# PCBv2_5a.net
KiCad netlist of a schematic drawn in EasyEDA
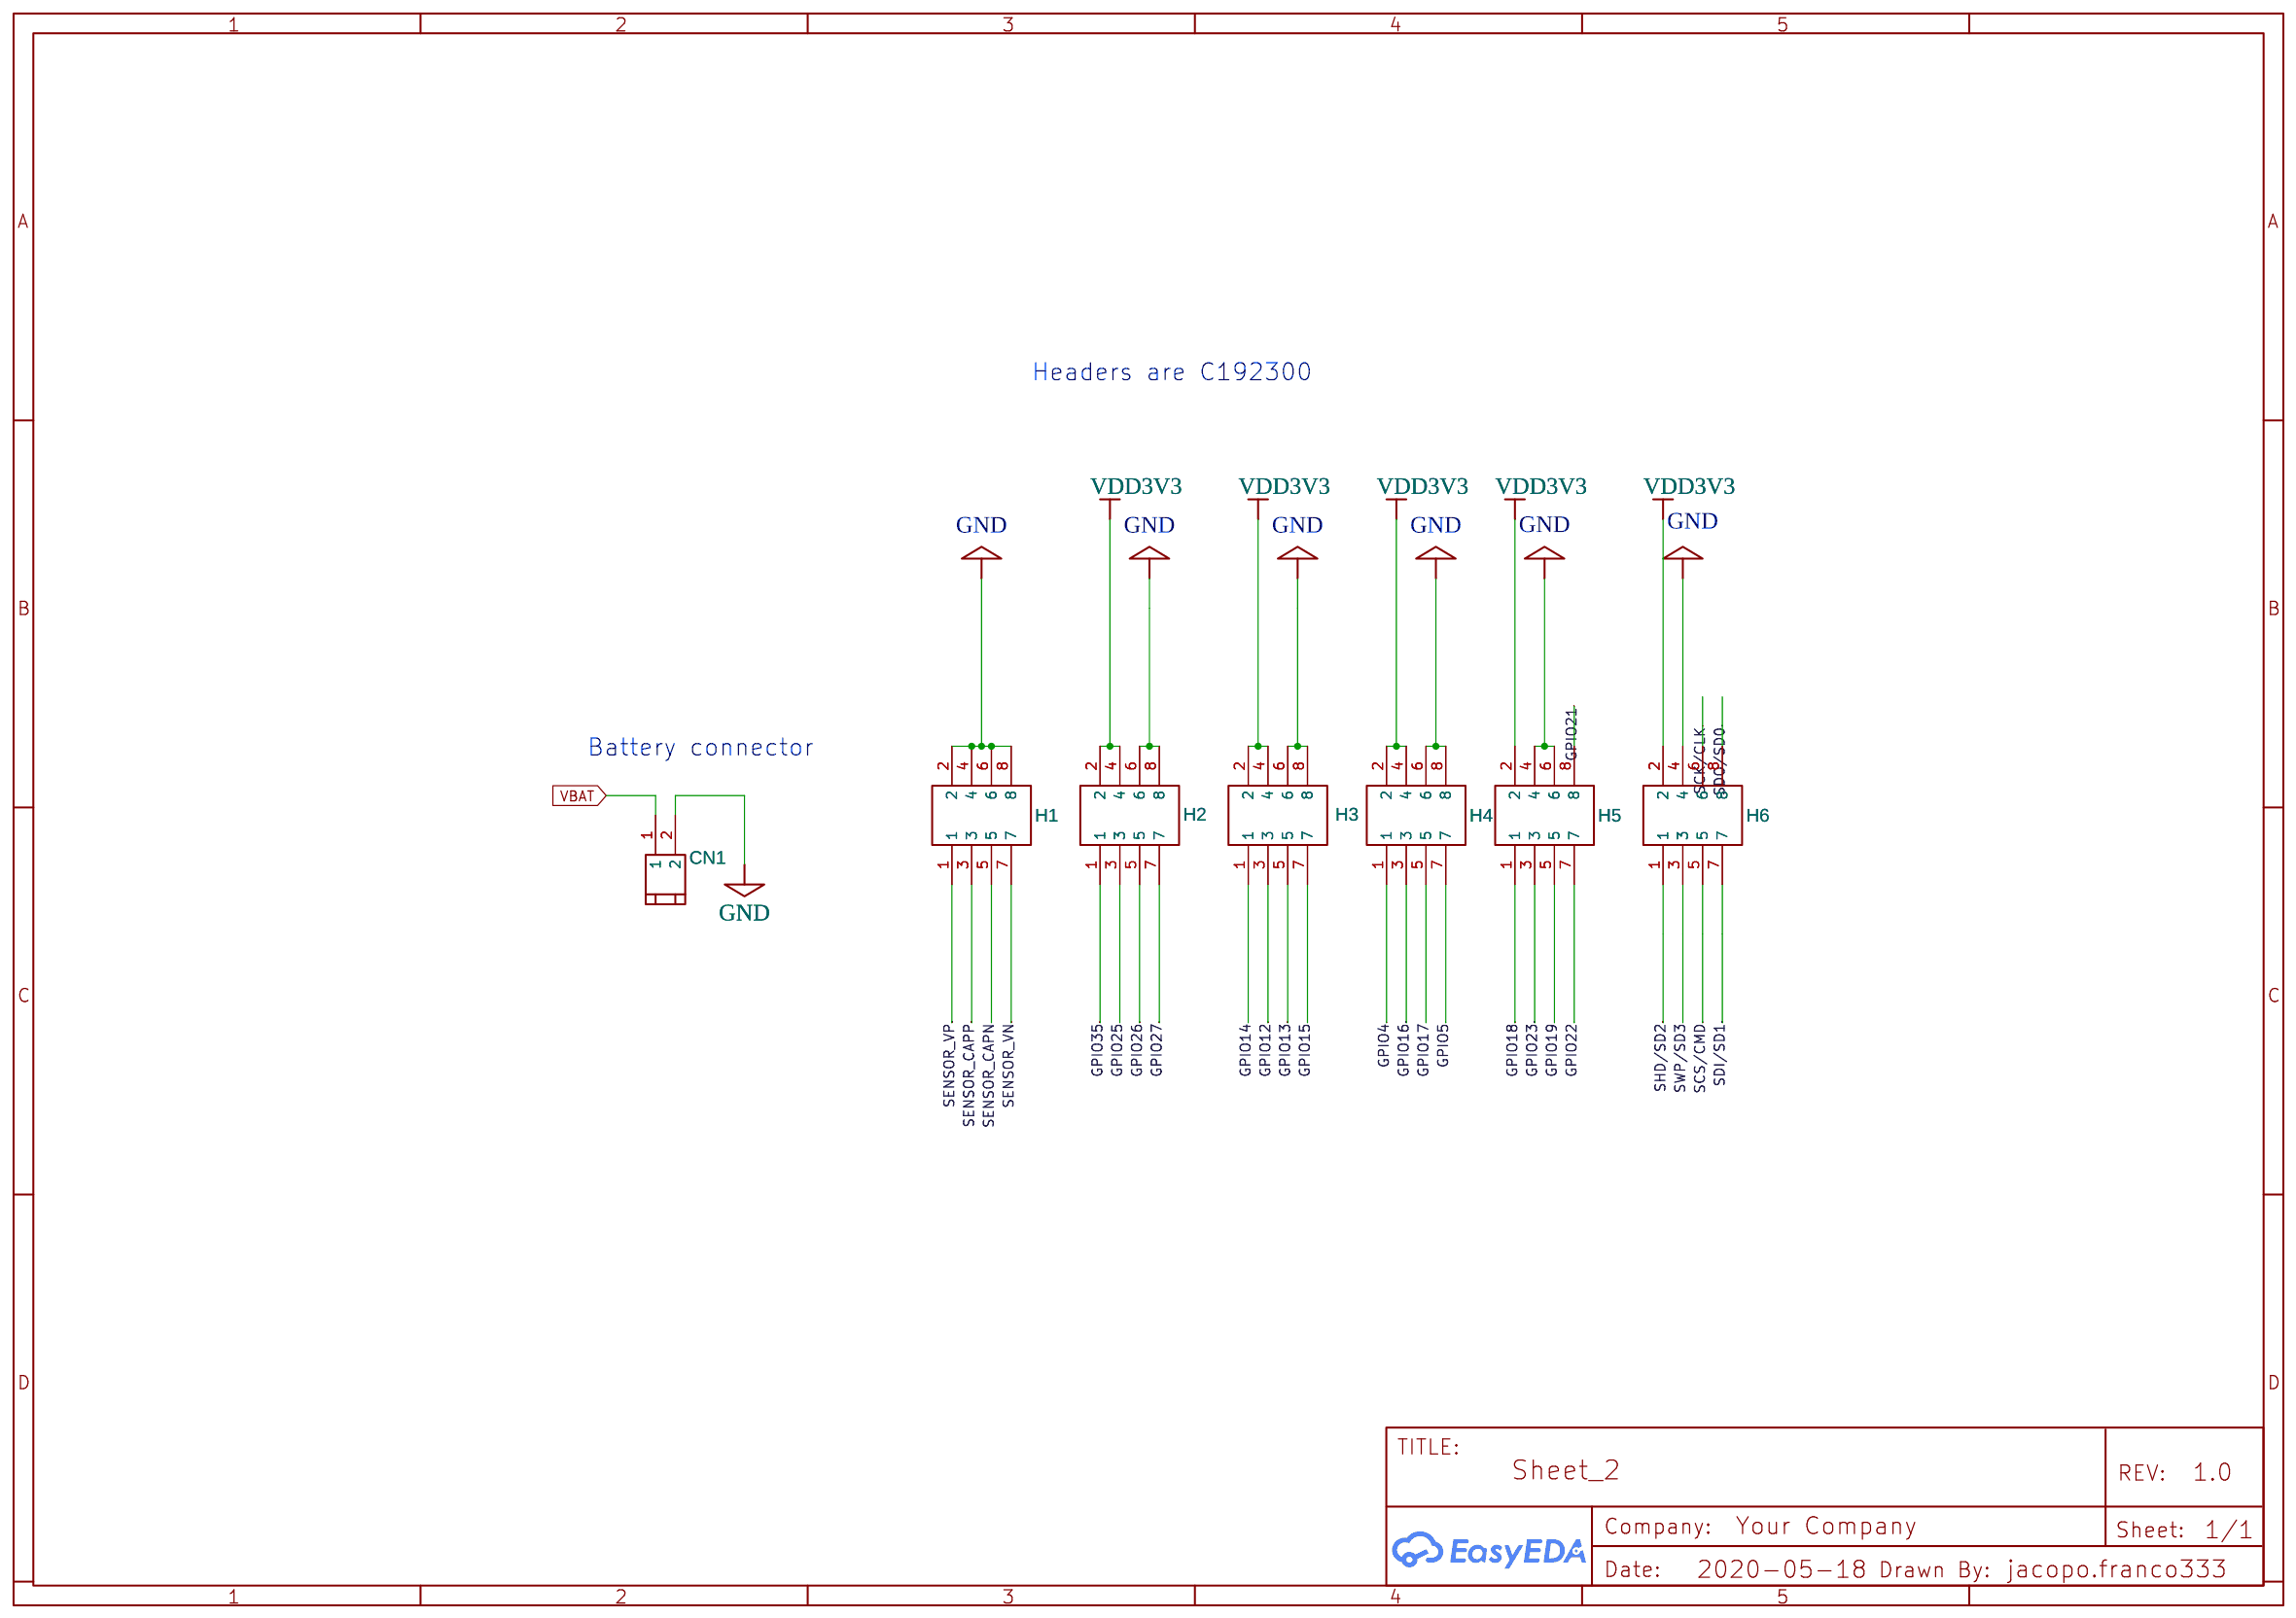
[diagram p0: Headers]
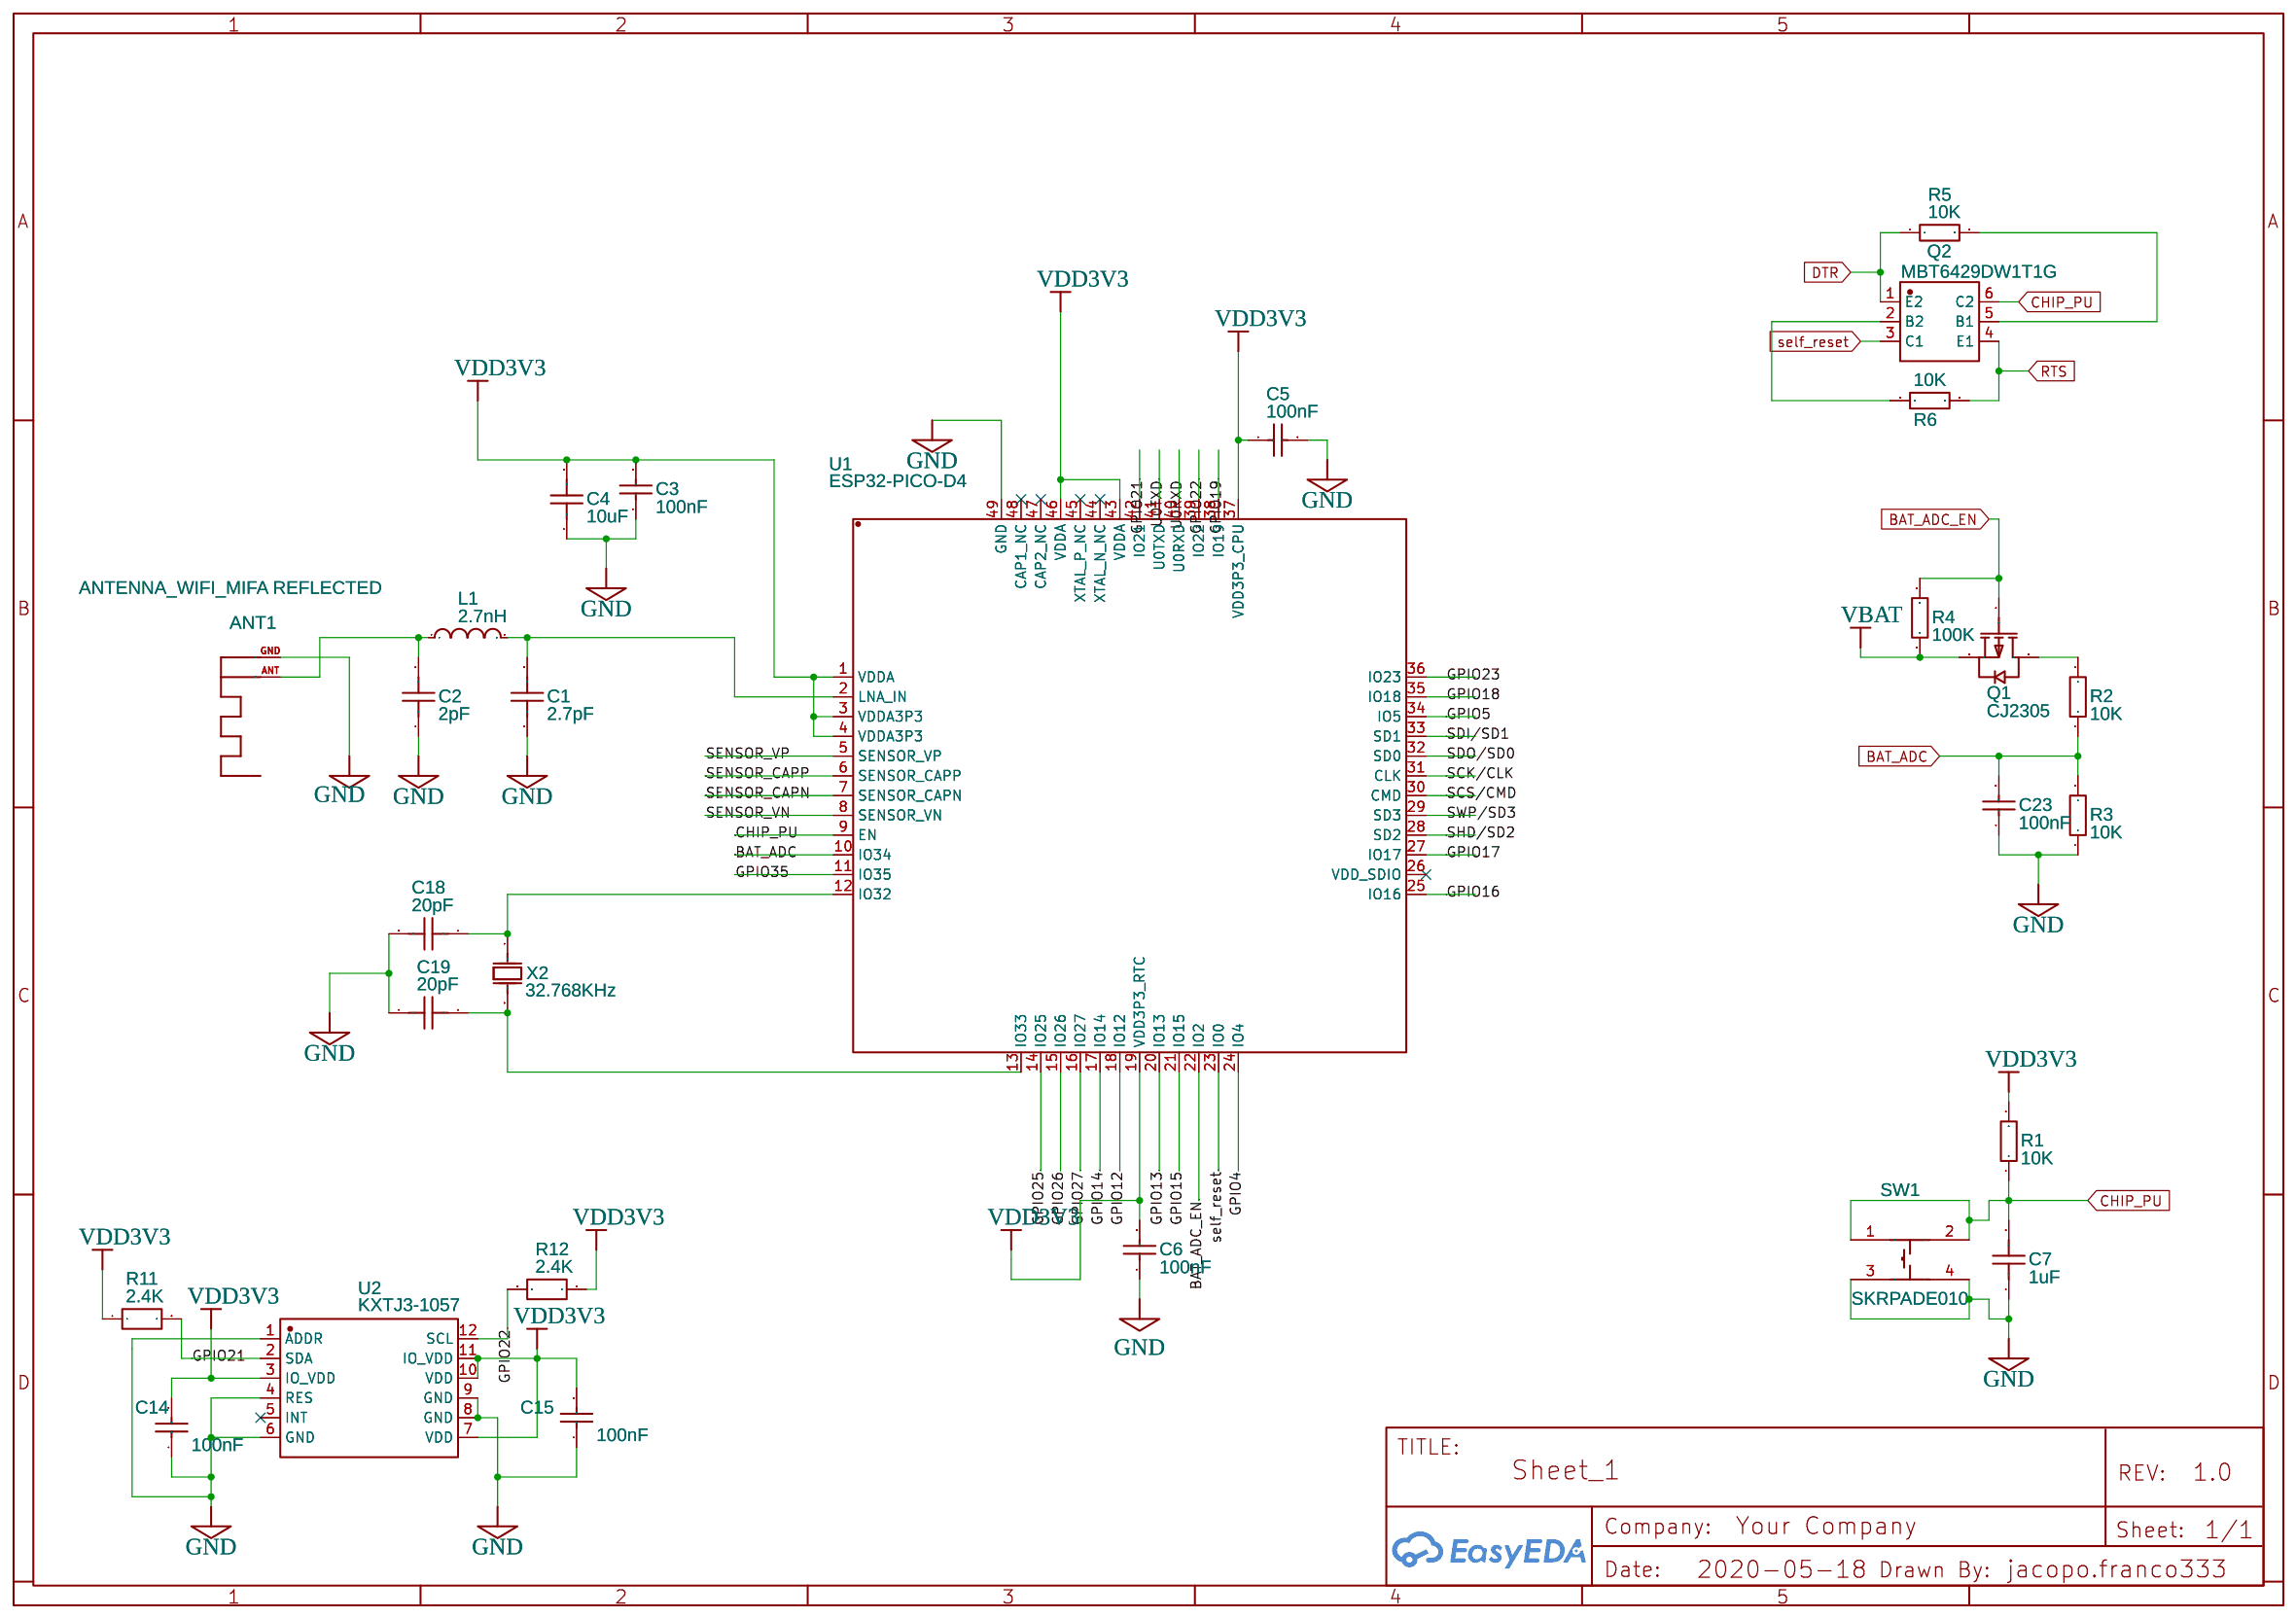
[diagram p1: ESP32]
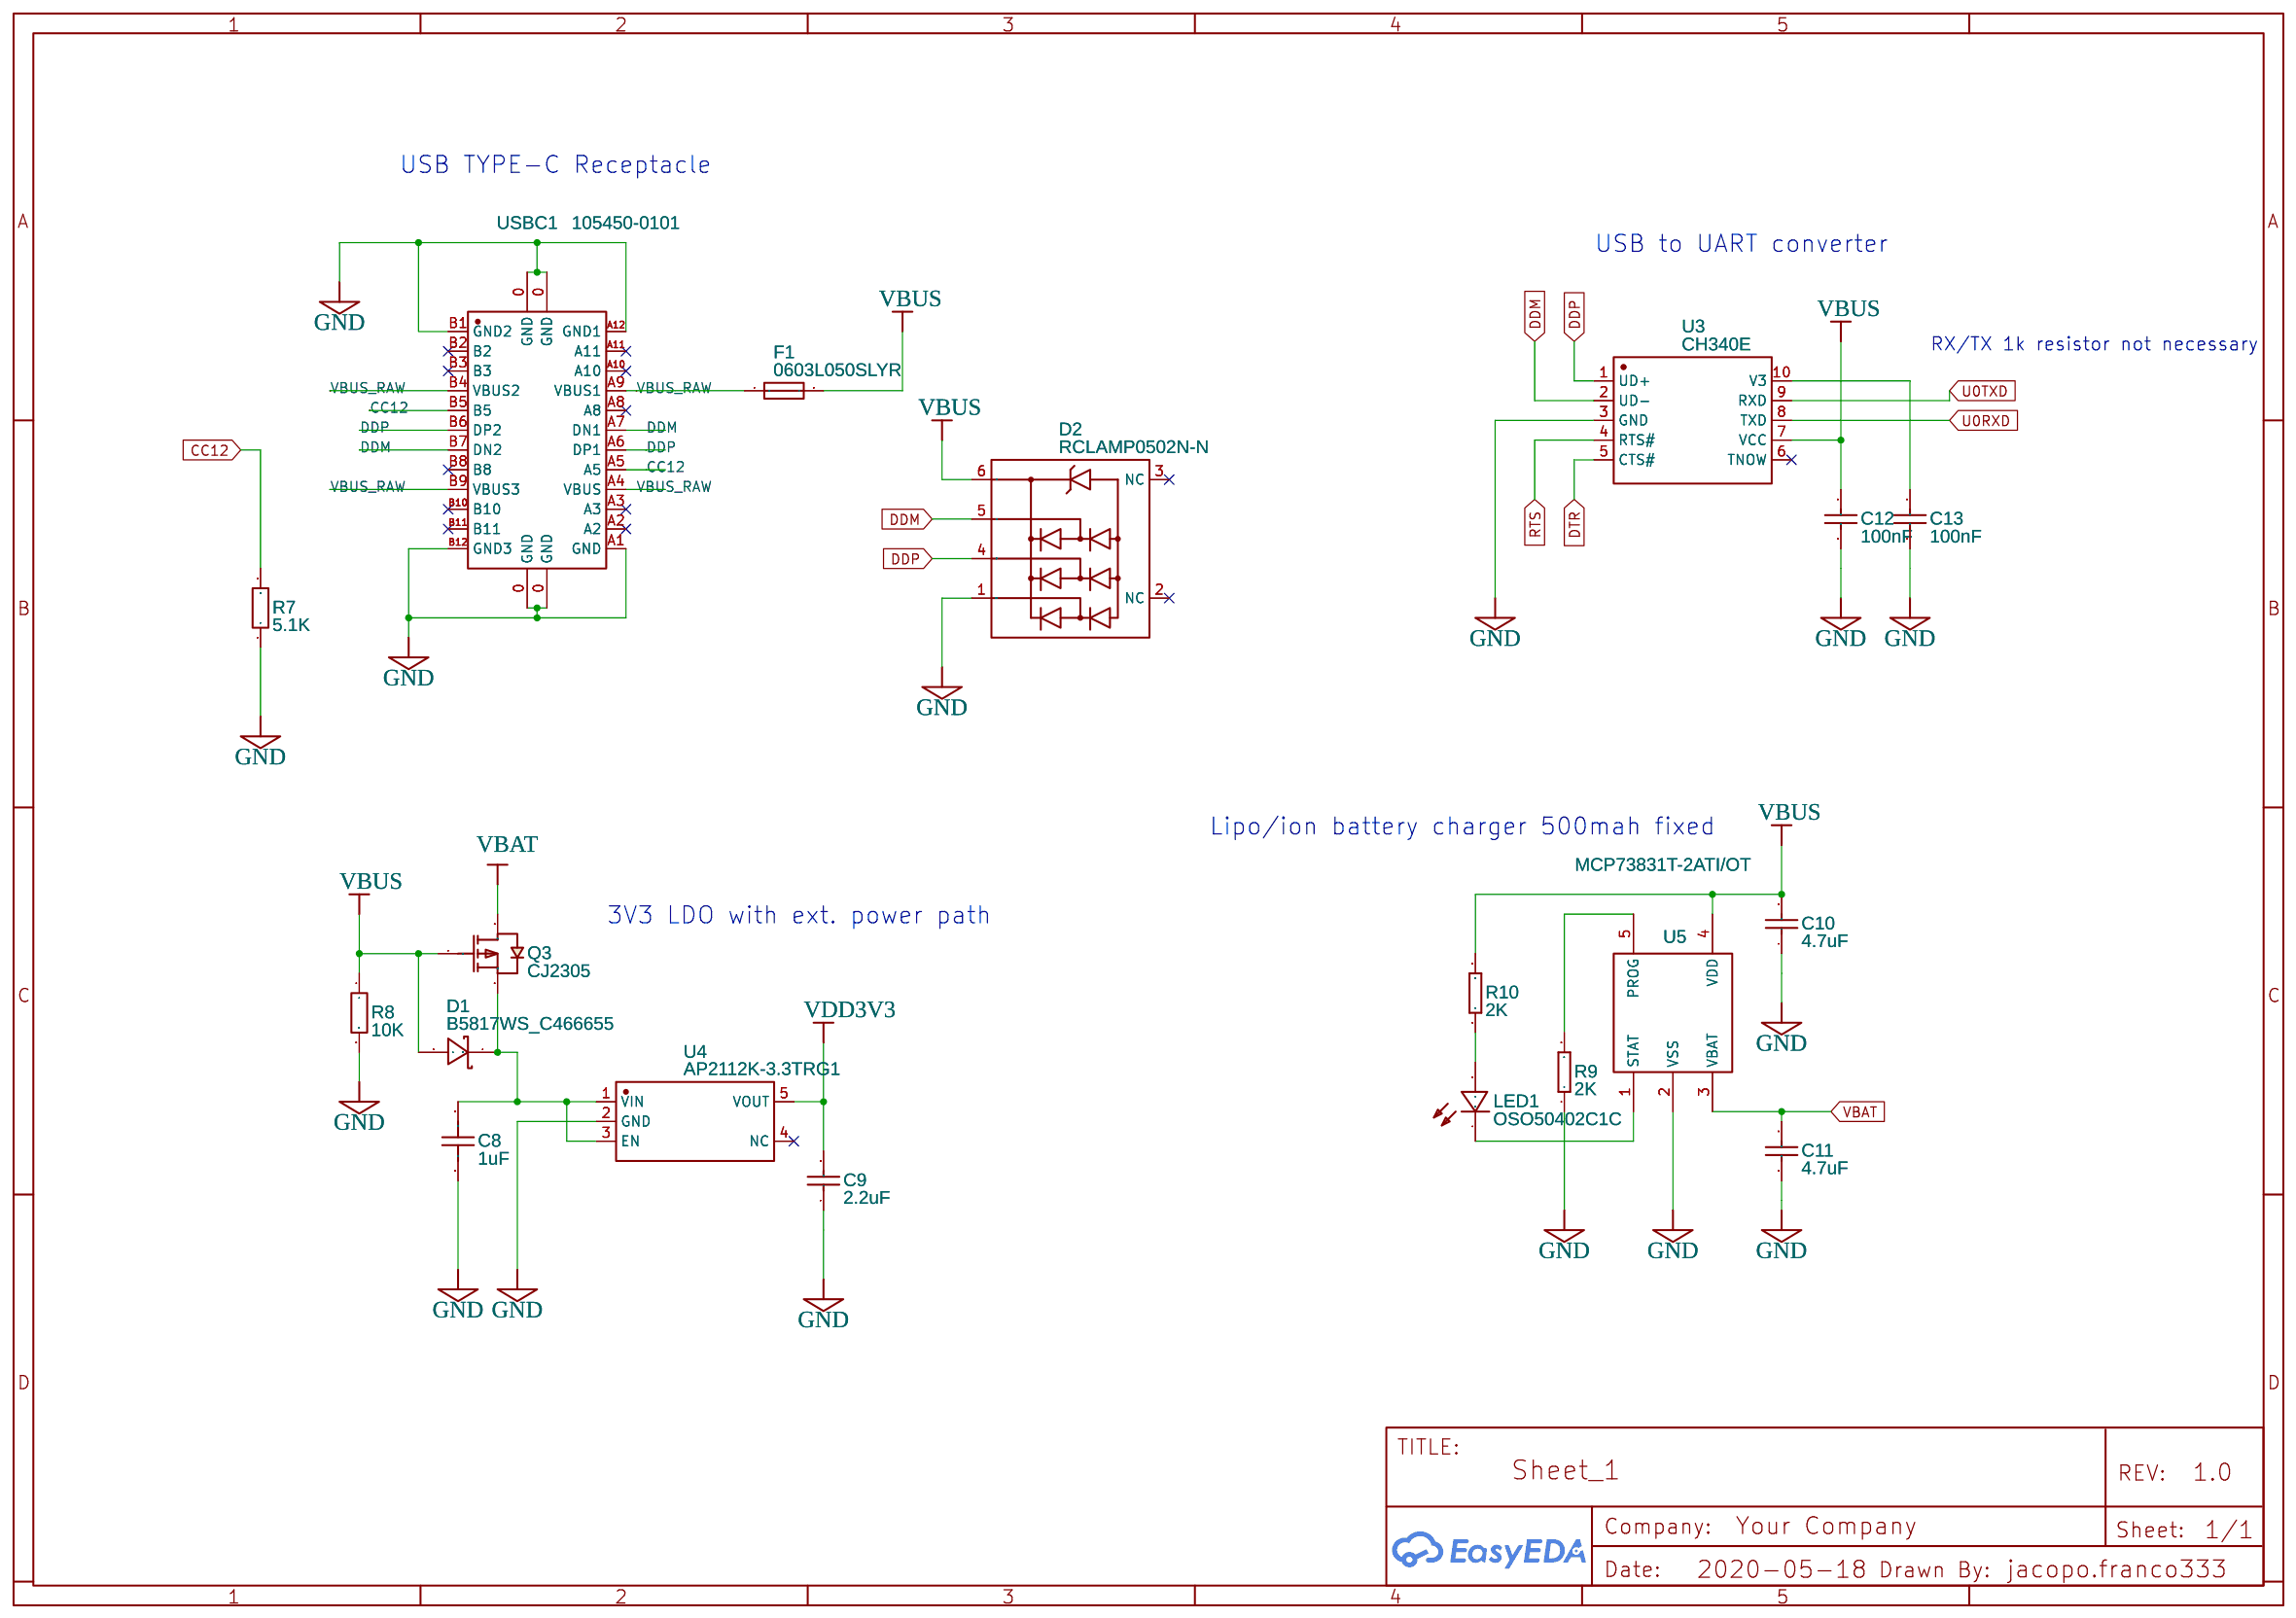
[diagram p2: Power, USB]

(export (version "E")
  (design (tool "Eeschema 10.0.6"))
  (components
    (comp (ref "CN1")
      (value "XH-2PWB")
      (fields (field (name "BOM_Supplier Part") "C64520"))
      (libsource (lib "") (part "XH-2PWB"))
    )
    (comp (ref "H1")
      (value "95278-801A08LF")
      (fields (field (name "BOM_Supplier Part") "C192300"))
      (libsource (lib "") (part "95278-801A08LF"))
    )
    (comp (ref "H2")
      (value "95278-801A08LF")
      (fields (field (name "BOM_Supplier Part") "C192300"))
      (libsource (lib "") (part "95278-801A08LF"))
    )
    (comp (ref "H3")
      (value "95278-801A08LF")
      (fields (field (name "BOM_Supplier Part") "C192300"))
      (libsource (lib "") (part "95278-801A08LF"))
    )
    (comp (ref "H4")
      (value "95278-801A08LF")
      (fields (field (name "BOM_Supplier Part") "C192300"))
      (libsource (lib "") (part "95278-801A08LF"))
    )
    (comp (ref "H5")
      (value "95278-801A08LF")
      (fields (field (name "BOM_Supplier Part") "C192300"))
      (libsource (lib "") (part "95278-801A08LF"))
    )
    (comp (ref "H6")
      (value "95278-801A08LF")
      (fields (field (name "BOM_Supplier Part") "C192300"))
      (libsource (lib "") (part "95278-801A08LF"))
    )
    (comp (ref "ANT1")
      (value "ANTENNA_WIFI_MIFA REFLECTED")
      (libsource (lib "") (part "ANTENNA_WIFI_MIFA REFLECTED"))
    )
    (comp (ref "C1")
      (value "2.7pF")
      (fields
        (field (name "BOM_Manufacturer Part") "CC0402CRNPO9BN2R7")
        (field (name "BOM_Supplier Part") "C277484")
      )
      (libsource (lib "") (part "CC0402CRNPO9BN2R7"))
    )
    (comp (ref "C2")
      (value "2pF")
      (fields
        (field (name "BOM_Manufacturer Part") "GJM1555C1H2R0WB01D")
        (field (name "BOM_Supplier Part") "C88885")
      )
      (libsource (lib "") (part "GJM1555C1H2R0WB01D"))
    )
    (comp (ref "C3")
      (value "100nF")
      (fields
        (field (name "BOM_Manufacturer Part") "GCM155R71E104KE02D")
        (field (name "BOM_Supplier Part") "C126527")
      )
      (libsource (lib "") (part "GCM155R71E104KE02D"))
    )
    (comp (ref "C4")
      (value "10uF")
      (fields
        (field (name "BOM_Manufacturer Part") "GRM155R61A106ME21D")
        (field (name "BOM_Supplier Part") "C324476")
      )
      (libsource (lib "") (part "GRM155R61A106ME21D"))
    )
    (comp (ref "C5")
      (value "100nF")
      (fields
        (field (name "BOM_Manufacturer Part") "GCM155R71E104KE02D")
        (field (name "BOM_Supplier Part") "C126527")
      )
      (libsource (lib "") (part "GCM155R71E104KE02D_1"))
    )
    (comp (ref "C6")
      (value "100nF")
      (fields
        (field (name "BOM_Manufacturer Part") "GCM155R71E104KE02D")
        (field (name "BOM_Supplier Part") "C126527")
      )
      (libsource (lib "") (part "GCM155R71E104KE02D"))
    )
    (comp (ref "C7")
      (value "1uF")
      (fields
        (field (name "BOM_Manufacturer Part") "CL05A105KA5NQNC")
        (field (name "BOM_Supplier Part") "C52923")
      )
      (libsource (lib "") (part "CL05A105KA5NQNC"))
    )
    (comp (ref "C14")
      (value "100nF")
      (fields
        (field (name "BOM_Manufacturer Part") "GCM155R71E104KE02D")
        (field (name "BOM_Supplier Part") "C126527")
      )
      (libsource (lib "") (part "GCM155R71E104KE02D"))
    )
    (comp (ref "C15")
      (value "100nF")
      (fields
        (field (name "BOM_Manufacturer Part") "GCM155R71E104KE02D")
        (field (name "BOM_Supplier Part") "C126527")
      )
      (libsource (lib "") (part "GCM155R71E104KE02D"))
    )
    (comp (ref "C18")
      (value "20pF")
      (fields
        (field (name "BOM_Manufacturer Part") "GCM1555C1H200FA16D")
        (field (name "BOM_Supplier Part") "C437436")
      )
      (libsource (lib "") (part "GCM1555C1H200FA16D_1"))
    )
    (comp (ref "C19")
      (value "20pF")
      (fields
        (field (name "BOM_Manufacturer Part") "GCM1555C1H200FA16D")
        (field (name "BOM_Supplier Part") "C437436")
      )
      (libsource (lib "") (part "GCM1555C1H200FA16D"))
    )
    (comp (ref "C23")
      (value "100nF")
      (fields
        (field (name "BOM_Manufacturer Part") "GCM155R71E104KE02D")
        (field (name "BOM_Supplier Part") "C126527")
      )
      (libsource (lib "") (part "GCM155R71E104KE02D"))
    )
    (comp (ref "L1")
      (value "2.7nH")
      (fields
        (field (name "BOM_Manufacturer Part") "MLG1005S2N7BT000")
        (field (name "BOM_Supplier Part") "C275282")
      )
      (libsource (lib "") (part "MLG1005S2N7BT000"))
    )
    (comp (ref "Q1")
      (value "CJ2305")
      (fields (field (name "BOM_Supplier Part") "C8549"))
      (libsource (lib "") (part "CJ2305"))
    )
    (comp (ref "Q2")
      (value "MBT6429DW1T1G")
      (fields (field (name "BOM_Supplier Part") "C463297"))
      (libsource (lib "") (part "MBT6429DW1T1G"))
    )
    (comp (ref "R1")
      (value "10K")
      (fields
        (field (name "BOM_Manufacturer Part") "RC0402FR-0710KL")
        (field (name "BOM_Supplier Part") "C60490")
      )
      (libsource (lib "") (part "RC0402FR-0710KL"))
    )
    (comp (ref "R2")
      (value "10K")
      (fields
        (field (name "BOM_Manufacturer Part") "RC0402FR-0710KL")
        (field (name "BOM_Supplier Part") "C60490")
      )
      (libsource (lib "") (part "RC0402FR-0710KL"))
    )
    (comp (ref "R3")
      (value "10K")
      (fields
        (field (name "BOM_Manufacturer Part") "RC0402FR-0710KL")
        (field (name "BOM_Supplier Part") "C60490")
      )
      (libsource (lib "") (part "RC0402FR-0710KL"))
    )
    (comp (ref "R4")
      (value "100K")
      (fields
        (field (name "BOM_Manufacturer Part") "0402WGJ0104TCE")
        (field (name "BOM_Supplier Part") "C25530")
      )
      (libsource (lib "") (part "0402WGJ0104TCE"))
    )
    (comp (ref "R5")
      (value "10K")
      (fields
        (field (name "BOM_Manufacturer Part") "RC0402FR-0710KL")
        (field (name "BOM_Supplier Part") "C60490")
      )
      (libsource (lib "") (part "RC0402FR-0710KL_1"))
    )
    (comp (ref "R6")
      (value "10K")
      (fields
        (field (name "BOM_Manufacturer Part") "RC0402FR-0710KL")
        (field (name "BOM_Supplier Part") "C60490")
      )
      (libsource (lib "") (part "RC0402FR-0710KL_1"))
    )
    (comp (ref "R11")
      (value "2.4K")
      (fields
        (field (name "BOM_Manufacturer Part") "0402WGD2401TCE")
        (field (name "BOM_Supplier Part") "C407742")
      )
      (libsource (lib "") (part "0402WGD2401TCE_1"))
    )
    (comp (ref "R12")
      (value "2.4K")
      (fields
        (field (name "BOM_Manufacturer Part") "0402WGD2401TCE")
        (field (name "BOM_Supplier Part") "C407742")
      )
      (libsource (lib "") (part "0402WGD2401TCE"))
    )
    (comp (ref "SW1")
      (value "SKRPADE010")
      (fields (field (name "BOM_Supplier Part") "C127488"))
      (libsource (lib "") (part "SKRPADE010"))
    )
    (comp (ref "U1")
      (value "ESP32-PICO-D4")
      (fields (field (name "BOM_Supplier Part") "C193707"))
      (libsource (lib "") (part "ESP32-PICO-D4"))
    )
    (comp (ref "U2")
      (value "KXTJ3-1057")
      (fields (field (name "BOM_Supplier Part") "C442603"))
      (libsource (lib "") (part "KXTJ3-1057"))
    )
    (comp (ref "X2")
      (value "32.768KHz")
      (fields
        (field (name "BOM_Manufacturer Part") "AH03270014")
        (field (name "BOM_Supplier Part") "C409356")
      )
      (libsource (lib "") (part "AH03270014"))
    )
    (comp (ref "C8")
      (value "1uF")
      (fields
        (field (name "BOM_Manufacturer Part") "CL05A105KA5NQNC")
        (field (name "BOM_Supplier Part") "C52923")
      )
      (libsource (lib "") (part "CL05A105KA5NQNC"))
    )
    (comp (ref "C9")
      (value "2.2uF")
      (fields
        (field (name "BOM_Manufacturer Part") "GRM155R61A225KE95D")
        (field (name "BOM_Supplier Part") "C77002")
      )
      (libsource (lib "") (part "GRM155R61A225KE95D"))
    )
    (comp (ref "C10")
      (value "4.7uF")
      (fields
        (field (name "BOM_Manufacturer Part") "GRM155R61A475KEAAD")
        (field (name "BOM_Supplier Part") "C77004")
      )
      (libsource (lib "") (part "GRM155R61A475KEAAD"))
    )
    (comp (ref "C11")
      (value "4.7uF")
      (fields
        (field (name "BOM_Manufacturer Part") "GRM155R61A475KEAAD")
        (field (name "BOM_Supplier Part") "C77004")
      )
      (libsource (lib "") (part "GRM155R61A475KEAAD"))
    )
    (comp (ref "C12")
      (value "100nF")
      (fields
        (field (name "BOM_Manufacturer Part") "GCM155R71E104KE02D")
        (field (name "BOM_Supplier Part") "C126527")
      )
      (libsource (lib "") (part "GCM155R71E104KE02D"))
    )
    (comp (ref "C13")
      (value "100nF")
      (fields
        (field (name "BOM_Manufacturer Part") "GCM155R71E104KE02D")
        (field (name "BOM_Supplier Part") "C126527")
      )
      (libsource (lib "") (part "GCM155R71E104KE02D"))
    )
    (comp (ref "D1")
      (value "B5817WS_C466655")
      (fields (field (name "BOM_Manufacturer Part") "B5817WS") (field (name "BOM_Supplier Part") "C466655"))
      (libsource (lib "") (part "B5817WS_C466655"))
    )
    (comp (ref "D2")
      (value "RCLAMP0502N-N")
      (fields
        (field (name "BOM_Manufacturer Part") "Rclamp0502N-N")
        (field (name "BOM_Supplier Part") "C344005")
      )
      (libsource (lib "") (part "RCLAMP0502N-N"))
    )
    (comp (ref "F1")
      (value "0603L050SLYR")
      (fields (field (name "BOM_Supplier Part") "C207014"))
      (libsource (lib "") (part "0603L050SLYR"))
    )
    (comp (ref "LED1")
      (value "OSO50402C1C")
      (fields (field (name "BOM_Supplier Part") "C268301"))
      (libsource (lib "") (part "OSO50402C1C"))
    )
    (comp (ref "Q3")
      (value "CJ2305")
      (fields (field (name "BOM_Supplier Part") "C8549"))
      (libsource (lib "") (part "CJ2305"))
    )
    (comp (ref "R7")
      (value "5.1K")
      (fields
        (field (name "BOM_Manufacturer Part") "AR02DTD5101")
        (field (name "BOM_Supplier Part") "C319557")
      )
      (libsource (lib "") (part "AR02DTD5101"))
    )
    (comp (ref "R8")
      (value "10K")
      (fields
        (field (name "BOM_Manufacturer Part") "RC0402FR-0710KL")
        (field (name "BOM_Supplier Part") "C60490")
      )
      (libsource (lib "") (part "RC0402FR-0710KL"))
    )
    (comp (ref "R9")
      (value "2K")
      (fields (field (name "BOM_Supplier Part") "C478870"))
      (libsource (lib "") (part "RESISTOR-0402"))
    )
    (comp (ref "R10")
      (value "2K")
      (fields (field (name "BOM_Supplier Part") "C478870"))
      (libsource (lib "") (part "RESISTOR-0402"))
    )
    (comp (ref "U3")
      (value "CH340E")
      (fields (field (name "BOM_Supplier Part") "C99652"))
      (libsource (lib "") (part "CH340E"))
    )
    (comp (ref "U4")
      (value "AP2112K-3.3TRG1")
      (fields (field (name "BOM_Supplier Part") "C51118"))
      (libsource (lib "") (part "AP2112K-3.3TRG1"))
    )
    (comp (ref "U5")
      (value "MCP73831T-2ATI/OT")
      (fields (field (name "BOM_Supplier Part") "C14879"))
      (libsource (lib "") (part "MCP73831T-2ATI/OT"))
    )
    (comp (ref "USBC1")
      (value "105450-0101")
      (fields (field (name "BOM_Supplier Part") "C134092"))
      (libsource (lib "") (part "105450-0101"))
    )
  )
  (nets
    (net (code "1") (name "BAT_ADC") (class "Default")
      (node (ref "C23") (pin "2") (pinfunction "2_2") (pintype "input"))
      (node (ref "R2") (pin "1") (pinfunction "1_1") (pintype "input"))
      (node (ref "R3") (pin "2") (pinfunction "2_2") (pintype "input"))
      (node (ref "U1") (pin "10") (pinfunction "IO34_10") (pintype "unspecified"))
    )
    (net (code "2") (name "BAT_ADC_EN") (class "Default")
      (node (ref "Q1") (pin "1") (pinfunction "G_1") (pintype "unspecified"))
      (node (ref "R4") (pin "2") (pinfunction "2_2") (pintype "input"))
      (node (ref "U1") (pin "22") (pinfunction "IO2_22") (pintype "unspecified"))
    )
    (net (code "3") (name "CC12") (class "Default")
      (node (ref "R7") (pin "2") (pinfunction "2_2") (pintype "unspecified"))
      (node (ref "USBC1") (pin "A5") (pinfunction "A5_A5") (pintype "unspecified"))
      (node (ref "USBC1") (pin "B5") (pinfunction "B5_B5") (pintype "unspecified"))
    )
    (net (code "4") (name "CHIP_PU") (class "Default")
      (node (ref "C7") (pin "2") (pinfunction "2_2") (pintype "unspecified"))
      (node (ref "Q2") (pin "6") (pinfunction "C2_6") (pintype "unspecified"))
      (node (ref "R1") (pin "1") (pinfunction "1_1") (pintype "input"))
      (node (ref "SW1") (pin "1") (pinfunction "1_1") (pintype "unspecified"))
      (node (ref "SW1") (pin "2") (pinfunction "2_2") (pintype "unspecified"))
      (node (ref "U1") (pin "9") (pinfunction "EN_9") (pintype "unspecified"))
    )
    (net (code "5") (name "DDM") (class "Default")
      (node (ref "D2") (pin "5") (pinfunction "I/O_5") (pintype "unspecified"))
      (node (ref "U3") (pin "2") (pinfunction "UD-_2") (pintype "unspecified"))
      (node (ref "USBC1") (pin "A7") (pinfunction "DN1_A7") (pintype "unspecified"))
      (node (ref "USBC1") (pin "B7") (pinfunction "DN2_B7") (pintype "unspecified"))
    )
    (net (code "6") (name "DDP") (class "Default")
      (node (ref "D2") (pin "4") (pinfunction "I/O_4") (pintype "unspecified"))
      (node (ref "U3") (pin "1") (pinfunction "UD+_1") (pintype "unspecified"))
      (node (ref "USBC1") (pin "A6") (pinfunction "DP1_A6") (pintype "unspecified"))
      (node (ref "USBC1") (pin "B6") (pinfunction "DP2_B6") (pintype "unspecified"))
    )
    (net (code "7") (name "DTR") (class "Default")
      (node (ref "Q2") (pin "1") (pinfunction "E2_1") (pintype "unspecified"))
      (node (ref "R5") (pin "1") (pinfunction "1_1") (pintype "input"))
      (node (ref "U3") (pin "5") (pinfunction "CTS#_5") (pintype "unspecified"))
    )
    (net (code "8") (name "GND") (class "Default")
      (node (ref "ANT1") (pin "GND") (pinfunction "GND_GND") (pintype "unspecified"))
      (node (ref "C1") (pin "1") (pinfunction "1_1") (pintype "unspecified"))
      (node (ref "C10") (pin "1") (pinfunction "1_1") (pintype "input"))
      (node (ref "C11") (pin "1") (pinfunction "1_1") (pintype "input"))
      (node (ref "C12") (pin "1") (pinfunction "1_1") (pintype "input"))
      (node (ref "C13") (pin "1") (pinfunction "1_1") (pintype "input"))
      (node (ref "C14") (pin "1") (pinfunction "1_1") (pintype "input"))
      (node (ref "C15") (pin "1") (pinfunction "1_1") (pintype "input"))
      (node (ref "C18") (pin "2") (pinfunction "2_2") (pintype "unspecified"))
      (node (ref "C19") (pin "1") (pinfunction "1_1") (pintype "unspecified"))
      (node (ref "C2") (pin "1") (pinfunction "1_1") (pintype "unspecified"))
      (node (ref "C23") (pin "1") (pinfunction "1_1") (pintype "input"))
      (node (ref "C3") (pin "1") (pinfunction "1_1") (pintype "input"))
      (node (ref "C4") (pin "1") (pinfunction "1_1") (pintype "unspecified"))
      (node (ref "C5") (pin "2") (pinfunction "2_2") (pintype "input"))
      (node (ref "C6") (pin "1") (pinfunction "1_1") (pintype "input"))
      (node (ref "C7") (pin "1") (pinfunction "1_1") (pintype "unspecified"))
      (node (ref "C8") (pin "1") (pinfunction "1_1") (pintype "unspecified"))
      (node (ref "C9") (pin "1") (pinfunction "1_1") (pintype "input"))
      (node (ref "CN1") (pin "2") (pinfunction "2_2") (pintype "unspecified"))
      (node (ref "D2") (pin "1") (pinfunction "GND_1") (pintype "unspecified"))
      (node (ref "H1") (pin "2") (pinfunction "2_2") (pintype "unspecified"))
      (node (ref "H1") (pin "4") (pinfunction "4_4") (pintype "unspecified"))
      (node (ref "H1") (pin "6") (pinfunction "6_6") (pintype "unspecified"))
      (node (ref "H1") (pin "8") (pinfunction "8_8") (pintype "unspecified"))
      (node (ref "H2") (pin "6") (pinfunction "6_6") (pintype "unspecified"))
      (node (ref "H2") (pin "8") (pinfunction "8_8") (pintype "unspecified"))
      (node (ref "H3") (pin "6") (pinfunction "6_6") (pintype "unspecified"))
      (node (ref "H3") (pin "8") (pinfunction "8_8") (pintype "unspecified"))
      (node (ref "H4") (pin "6") (pinfunction "6_6") (pintype "unspecified"))
      (node (ref "H4") (pin "8") (pinfunction "8_8") (pintype "unspecified"))
      (node (ref "H5") (pin "4") (pinfunction "4_4") (pintype "unspecified"))
      (node (ref "H5") (pin "6") (pinfunction "6_6") (pintype "unspecified"))
      (node (ref "H6") (pin "4") (pinfunction "4_4") (pintype "unspecified"))
      (node (ref "R3") (pin "1") (pinfunction "1_1") (pintype "input"))
      (node (ref "R7") (pin "1") (pinfunction "1_1") (pintype "unspecified"))
      (node (ref "R8") (pin "2") (pinfunction "2_2") (pintype "input"))
      (node (ref "R9") (pin "1") (pinfunction "1_1") (pintype "unspecified"))
      (node (ref "SW1") (pin "3") (pinfunction "3_3") (pintype "unspecified"))
      (node (ref "SW1") (pin "4") (pinfunction "4_4") (pintype "unspecified"))
      (node (ref "U1") (pin "49") (pinfunction "GND_49") (pintype "unspecified"))
      (node (ref "U2") (pin "1") (pinfunction "ADDR_1") (pintype "unspecified"))
      (node (ref "U2") (pin "4") (pinfunction "RES_4") (pintype "unspecified"))
      (node (ref "U2") (pin "6") (pinfunction "GND_6") (pintype "unspecified"))
      (node (ref "U2") (pin "8") (pinfunction "GND_8") (pintype "unspecified"))
      (node (ref "U2") (pin "9") (pinfunction "GND_9") (pintype "unspecified"))
      (node (ref "U3") (pin "3") (pinfunction "GND_3") (pintype "unspecified"))
      (node (ref "U4") (pin "2") (pinfunction "GND_2") (pintype "unspecified"))
      (node (ref "U5") (pin "2") (pinfunction "VSS_2") (pintype "unspecified"))
      (node (ref "USBC1") (pin "0") (pinfunction "GND_0") (pintype "unspecified"))
      (node (ref "USBC1") (pin "A1") (pinfunction "GND_A1") (pintype "unspecified"))
      (node (ref "USBC1") (pin "A12") (pinfunction "GND1_A12") (pintype "unspecified"))
      (node (ref "USBC1") (pin "B1") (pinfunction "GND2_B1") (pintype "unspecified"))
      (node (ref "USBC1") (pin "B12") (pinfunction "GND3_B12") (pintype "unspecified"))
    )
    (net (code "9") (name "GPIO4") (class "Default")
      (node (ref "H4") (pin "1") (pinfunction "1_1") (pintype "unspecified"))
      (node (ref "U1") (pin "24") (pinfunction "IO4_24") (pintype "unspecified"))
    )
    (net (code "10") (name "GPIO5") (class "Default")
      (node (ref "H4") (pin "7") (pinfunction "7_7") (pintype "unspecified"))
      (node (ref "U1") (pin "34") (pinfunction "IO5_34") (pintype "unspecified"))
    )
    (net (code "11") (name "GPIO12") (class "Default")
      (node (ref "H3") (pin "3") (pinfunction "3_3") (pintype "unspecified"))
      (node (ref "U1") (pin "18") (pinfunction "IO12_18") (pintype "unspecified"))
    )
    (net (code "12") (name "GPIO13") (class "Default")
      (node (ref "H3") (pin "5") (pinfunction "5_5") (pintype "unspecified"))
      (node (ref "U1") (pin "20") (pinfunction "IO13_20") (pintype "unspecified"))
    )
    (net (code "13") (name "GPIO14") (class "Default")
      (node (ref "H3") (pin "1") (pinfunction "1_1") (pintype "unspecified"))
      (node (ref "U1") (pin "17") (pinfunction "IO14_17") (pintype "unspecified"))
    )
    (net (code "14") (name "GPIO15") (class "Default")
      (node (ref "H3") (pin "7") (pinfunction "7_7") (pintype "unspecified"))
      (node (ref "U1") (pin "21") (pinfunction "IO15_21") (pintype "unspecified"))
    )
    (net (code "15") (name "GPIO16") (class "Default")
      (node (ref "H4") (pin "3") (pinfunction "3_3") (pintype "unspecified"))
      (node (ref "U1") (pin "25") (pinfunction "IO16_25") (pintype "unspecified"))
    )
    (net (code "16") (name "GPIO17") (class "Default")
      (node (ref "H4") (pin "5") (pinfunction "5_5") (pintype "unspecified"))
      (node (ref "U1") (pin "27") (pinfunction "IO17_27") (pintype "unspecified"))
    )
    (net (code "17") (name "GPIO18") (class "Default")
      (node (ref "H5") (pin "1") (pinfunction "1_1") (pintype "unspecified"))
      (node (ref "U1") (pin "35") (pinfunction "IO18_35") (pintype "unspecified"))
    )
    (net (code "18") (name "GPIO19") (class "Default")
      (node (ref "H5") (pin "5") (pinfunction "5_5") (pintype "unspecified"))
      (node (ref "U1") (pin "38") (pinfunction "IO19_38") (pintype "unspecified"))
    )
    (net (code "19") (name "GPIO21") (class "Default")
      (node (ref "H5") (pin "8") (pinfunction "8_8") (pintype "unspecified"))
      (node (ref "R11") (pin "2") (pinfunction "2_2") (pintype "unspecified"))
      (node (ref "U1") (pin "42") (pinfunction "IO21_42") (pintype "unspecified"))
      (node (ref "U2") (pin "2") (pinfunction "SDA_2") (pintype "unspecified"))
    )
    (net (code "20") (name "GPIO22") (class "Default")
      (node (ref "H5") (pin "7") (pinfunction "7_7") (pintype "unspecified"))
      (node (ref "R12") (pin "2") (pinfunction "2_2") (pintype "unspecified"))
      (node (ref "U1") (pin "39") (pinfunction "IO22_39") (pintype "unspecified"))
      (node (ref "U2") (pin "12") (pinfunction "SCL_12") (pintype "unspecified"))
    )
    (net (code "21") (name "GPIO23") (class "Default")
      (node (ref "H5") (pin "3") (pinfunction "3_3") (pintype "unspecified"))
      (node (ref "U1") (pin "36") (pinfunction "IO23_36") (pintype "unspecified"))
    )
    (net (code "22") (name "GPIO25") (class "Default")
      (node (ref "H2") (pin "3") (pinfunction "3_3") (pintype "unspecified"))
      (node (ref "U1") (pin "14") (pinfunction "IO25_14") (pintype "unspecified"))
    )
    (net (code "23") (name "GPIO26") (class "Default")
      (node (ref "H2") (pin "5") (pinfunction "5_5") (pintype "unspecified"))
      (node (ref "U1") (pin "15") (pinfunction "IO26_15") (pintype "unspecified"))
    )
    (net (code "24") (name "GPIO27") (class "Default")
      (node (ref "H2") (pin "7") (pinfunction "7_7") (pintype "unspecified"))
      (node (ref "U1") (pin "16") (pinfunction "IO27_16") (pintype "unspecified"))
    )
    (net (code "25") (name "GPIO35") (class "Default")
      (node (ref "H2") (pin "1") (pinfunction "1_1") (pintype "unspecified"))
      (node (ref "U1") (pin "11") (pinfunction "IO35_11") (pintype "unspecified"))
    )
    (net (code "26") (name "Net-(ANT1-PadANT)") (class "Default")
      (node (ref "ANT1") (pin "ANT") (pinfunction "ANT_ANT") (pintype "unspecified"))
      (node (ref "C2") (pin "2") (pinfunction "2_2") (pintype "unspecified"))
      (node (ref "L1") (pin "1") (pinfunction "1_1") (pintype "unspecified"))
    )
    (net (code "27") (name "Net-(D1-C)") (class "Default")
      (node (ref "C8") (pin "2") (pinfunction "2_2") (pintype "unspecified"))
      (node (ref "D1") (pin "1") (pinfunction "C_1") (pintype "unspecified"))
      (node (ref "Q3") (pin "2") (pinfunction "S_2") (pintype "unspecified"))
      (node (ref "U4") (pin "1") (pinfunction "VIN_1") (pintype "unspecified"))
      (node (ref "U4") (pin "3") (pinfunction "EN_3") (pintype "unspecified"))
    )
    (net (code "28") (name "Net-(LED1-A)") (class "Default")
      (node (ref "LED1") (pin "2") (pinfunction "A_2") (pintype "unspecified"))
      (node (ref "R10") (pin "1") (pinfunction "1_1") (pintype "unspecified"))
    )
    (net (code "29") (name "Net-(LED1-C)") (class "Default")
      (node (ref "LED1") (pin "1") (pinfunction "C_1") (pintype "unspecified"))
      (node (ref "U5") (pin "1") (pinfunction "STAT_1") (pintype "unspecified"))
    )
    (net (code "30") (name "Net-(Q1-D)") (class "Default")
      (node (ref "Q1") (pin "3") (pinfunction "D_3") (pintype "unspecified"))
      (node (ref "R2") (pin "2") (pinfunction "2_2") (pintype "input"))
    )
    (net (code "31") (name "Net-(Q2-B1)") (class "Default")
      (node (ref "Q2") (pin "5") (pinfunction "B1_5") (pintype "unspecified"))
      (node (ref "R5") (pin "2") (pinfunction "2_2") (pintype "input"))
    )
    (net (code "32") (name "Net-(Q2-B2)") (class "Default")
      (node (ref "Q2") (pin "2") (pinfunction "B2_2") (pintype "unspecified"))
      (node (ref "R6") (pin "1") (pinfunction "1_1") (pintype "input"))
    )
    (net (code "33") (name "Net-(U1-IO32)") (class "Default")
      (node (ref "C18") (pin "1") (pinfunction "1_1") (pintype "unspecified"))
      (node (ref "U1") (pin "12") (pinfunction "IO32_12") (pintype "unspecified"))
      (node (ref "X2") (pin "1") (pinfunction "OSC1_1") (pintype "input"))
    )
    (net (code "34") (name "Net-(U1-IO33)") (class "Default")
      (node (ref "C19") (pin "2") (pinfunction "2_2") (pintype "unspecified"))
      (node (ref "U1") (pin "13") (pinfunction "IO33_13") (pintype "unspecified"))
      (node (ref "X2") (pin "2") (pinfunction "OSC2_2") (pintype "input"))
    )
    (net (code "35") (name "Net-(U1-LNA_IN)") (class "Default")
      (node (ref "C1") (pin "2") (pinfunction "2_2") (pintype "unspecified"))
      (node (ref "L1") (pin "2") (pinfunction "2_2") (pintype "unspecified"))
      (node (ref "U1") (pin "2") (pinfunction "LNA_IN_2") (pintype "unspecified"))
    )
    (net (code "36") (name "Net-(U3-V3)") (class "Default")
      (node (ref "C13") (pin "2") (pinfunction "2_2") (pintype "input"))
      (node (ref "U3") (pin "10") (pinfunction "V3_10") (pintype "unspecified"))
    )
    (net (code "37") (name "Net-(U5-PROG)") (class "Default")
      (node (ref "R9") (pin "2") (pinfunction "2_2") (pintype "unspecified"))
      (node (ref "U5") (pin "5") (pinfunction "PROG_5") (pintype "unspecified"))
    )
    (net (code "38") (name "RTS") (class "Default")
      (node (ref "Q2") (pin "4") (pinfunction "E1_4") (pintype "unspecified"))
      (node (ref "R6") (pin "2") (pinfunction "2_2") (pintype "input"))
      (node (ref "U3") (pin "4") (pinfunction "RTS#_4") (pintype "unspecified"))
    )
    (net (code "39") (name "SCK{slash}CLK") (class "Default")
      (node (ref "H6") (pin "6") (pinfunction "6_6") (pintype "unspecified"))
      (node (ref "U1") (pin "31") (pinfunction "CLK_31") (pintype "unspecified"))
    )
    (net (code "40") (name "SCS{slash}CMD") (class "Default")
      (node (ref "H6") (pin "5") (pinfunction "5_5") (pintype "unspecified"))
      (node (ref "U1") (pin "30") (pinfunction "CMD_30") (pintype "unspecified"))
    )
    (net (code "41") (name "SDI{slash}SD1") (class "Default")
      (node (ref "H6") (pin "7") (pinfunction "7_7") (pintype "unspecified"))
      (node (ref "U1") (pin "33") (pinfunction "SD1_33") (pintype "unspecified"))
    )
    (net (code "42") (name "SDO{slash}SD0") (class "Default")
      (node (ref "H6") (pin "8") (pinfunction "8_8") (pintype "unspecified"))
      (node (ref "U1") (pin "32") (pinfunction "SD0_32") (pintype "unspecified"))
    )
    (net (code "43") (name "SENSOR_CAPN") (class "Default")
      (node (ref "H1") (pin "5") (pinfunction "5_5") (pintype "unspecified"))
      (node (ref "U1") (pin "7") (pinfunction "SENSOR_CAPN_7") (pintype "unspecified"))
    )
    (net (code "44") (name "SENSOR_CAPP") (class "Default")
      (node (ref "H1") (pin "3") (pinfunction "3_3") (pintype "unspecified"))
      (node (ref "U1") (pin "6") (pinfunction "SENSOR_CAPP_6") (pintype "unspecified"))
    )
    (net (code "45") (name "SENSOR_VN") (class "Default")
      (node (ref "H1") (pin "7") (pinfunction "7_7") (pintype "unspecified"))
      (node (ref "U1") (pin "8") (pinfunction "SENSOR_VN_8") (pintype "unspecified"))
    )
    (net (code "46") (name "SENSOR_VP") (class "Default")
      (node (ref "H1") (pin "1") (pinfunction "1_1") (pintype "unspecified"))
      (node (ref "U1") (pin "5") (pinfunction "SENSOR_VP_5") (pintype "unspecified"))
    )
    (net (code "47") (name "SHD{slash}SD2") (class "Default")
      (node (ref "H6") (pin "1") (pinfunction "1_1") (pintype "unspecified"))
      (node (ref "U1") (pin "28") (pinfunction "SD2_28") (pintype "unspecified"))
    )
    (net (code "48") (name "SWP{slash}SD3") (class "Default")
      (node (ref "H6") (pin "3") (pinfunction "3_3") (pintype "unspecified"))
      (node (ref "U1") (pin "29") (pinfunction "SD3_29") (pintype "unspecified"))
    )
    (net (code "49") (name "U0RXD") (class "Default")
      (node (ref "U1") (pin "40") (pinfunction "U0RXD_40") (pintype "unspecified"))
      (node (ref "U3") (pin "8") (pinfunction "TXD_8") (pintype "unspecified"))
    )
    (net (code "50") (name "U0TXD") (class "Default")
      (node (ref "U1") (pin "41") (pinfunction "U0TXD_41") (pintype "unspecified"))
      (node (ref "U3") (pin "9") (pinfunction "RXD_9") (pintype "unspecified"))
    )
    (net (code "51") (name "VBAT") (class "Default")
      (node (ref "C11") (pin "2") (pinfunction "2_2") (pintype "input"))
      (node (ref "CN1") (pin "1") (pinfunction "1_1") (pintype "unspecified"))
      (node (ref "Q1") (pin "2") (pinfunction "S_2") (pintype "unspecified"))
      (node (ref "Q3") (pin "3") (pinfunction "D_3") (pintype "unspecified"))
      (node (ref "R4") (pin "1") (pinfunction "1_1") (pintype "input"))
      (node (ref "U5") (pin "3") (pinfunction "VBAT_3") (pintype "unspecified"))
    )
    (net (code "52") (name "VBUS") (class "Default")
      (node (ref "C10") (pin "2") (pinfunction "2_2") (pintype "input"))
      (node (ref "C12") (pin "2") (pinfunction "2_2") (pintype "input"))
      (node (ref "D1") (pin "2") (pinfunction "A_2") (pintype "unspecified"))
      (node (ref "D2") (pin "6") (pinfunction "VBUS_6") (pintype "unspecified"))
      (node (ref "F1") (pin "2") (pinfunction "2_2") (pintype "unspecified"))
      (node (ref "Q3") (pin "1") (pinfunction "G_1") (pintype "unspecified"))
      (node (ref "R10") (pin "2") (pinfunction "2_2") (pintype "unspecified"))
      (node (ref "R8") (pin "1") (pinfunction "1_1") (pintype "input"))
      (node (ref "U3") (pin "7") (pinfunction "VCC_7") (pintype "unspecified"))
      (node (ref "U5") (pin "4") (pinfunction "VDD_4") (pintype "unspecified"))
    )
    (net (code "53") (name "VBUS_RAW") (class "Default")
      (node (ref "F1") (pin "1") (pinfunction "1_1") (pintype "unspecified"))
      (node (ref "USBC1") (pin "A4") (pinfunction "VBUS_A4") (pintype "unspecified"))
      (node (ref "USBC1") (pin "A9") (pinfunction "VBUS1_A9") (pintype "unspecified"))
      (node (ref "USBC1") (pin "B4") (pinfunction "VBUS2_B4") (pintype "unspecified"))
      (node (ref "USBC1") (pin "B9") (pinfunction "VBUS3_B9") (pintype "unspecified"))
    )
    (net (code "54") (name "VDD3V3") (class "Default")
      (node (ref "C14") (pin "2") (pinfunction "2_2") (pintype "input"))
      (node (ref "C15") (pin "2") (pinfunction "2_2") (pintype "input"))
      (node (ref "C3") (pin "2") (pinfunction "2_2") (pintype "input"))
      (node (ref "C4") (pin "2") (pinfunction "2_2") (pintype "unspecified"))
      (node (ref "C5") (pin "1") (pinfunction "1_1") (pintype "input"))
      (node (ref "C6") (pin "2") (pinfunction "2_2") (pintype "input"))
      (node (ref "C9") (pin "2") (pinfunction "2_2") (pintype "input"))
      (node (ref "H2") (pin "2") (pinfunction "2_2") (pintype "unspecified"))
      (node (ref "H2") (pin "4") (pinfunction "4_4") (pintype "unspecified"))
      (node (ref "H3") (pin "2") (pinfunction "2_2") (pintype "unspecified"))
      (node (ref "H3") (pin "4") (pinfunction "4_4") (pintype "unspecified"))
      (node (ref "H4") (pin "2") (pinfunction "2_2") (pintype "unspecified"))
      (node (ref "H4") (pin "4") (pinfunction "4_4") (pintype "unspecified"))
      (node (ref "H5") (pin "2") (pinfunction "2_2") (pintype "unspecified"))
      (node (ref "H6") (pin "2") (pinfunction "2_2") (pintype "unspecified"))
      (node (ref "R1") (pin "2") (pinfunction "2_2") (pintype "input"))
      (node (ref "R11") (pin "1") (pinfunction "1_1") (pintype "unspecified"))
      (node (ref "R12") (pin "1") (pinfunction "1_1") (pintype "unspecified"))
      (node (ref "U1") (pin "1") (pinfunction "VDDA_1") (pintype "unspecified"))
      (node (ref "U1") (pin "19") (pinfunction "VDD3P3_RTC_19") (pintype "unspecified"))
      (node (ref "U1") (pin "3") (pinfunction "VDDA3P3_3") (pintype "unspecified"))
      (node (ref "U1") (pin "37") (pinfunction "VDD3P3_CPU_37") (pintype "unspecified"))
      (node (ref "U1") (pin "4") (pinfunction "VDDA3P3_4") (pintype "unspecified"))
      (node (ref "U1") (pin "43") (pinfunction "VDDA_43") (pintype "unspecified"))
      (node (ref "U1") (pin "46") (pinfunction "VDDA_46") (pintype "unspecified"))
      (node (ref "U2") (pin "10") (pinfunction "VDD_10") (pintype "unspecified"))
      (node (ref "U2") (pin "11") (pinfunction "IO_VDD_11") (pintype "unspecified"))
      (node (ref "U2") (pin "3") (pinfunction "IO_VDD_3") (pintype "unspecified"))
      (node (ref "U2") (pin "7") (pinfunction "VDD_7") (pintype "unspecified"))
      (node (ref "U4") (pin "5") (pinfunction "VOUT_5") (pintype "unspecified"))
    )
    (net (code "55") (name "self_reset") (class "Default")
      (node (ref "Q2") (pin "3") (pinfunction "C1_3") (pintype "unspecified"))
      (node (ref "U1") (pin "23") (pinfunction "IO0_23") (pintype "unspecified"))
    )
    (net (code "56") (name "unconnected-(D2-NC-Pad2)") (class "Default")
      (node (ref "D2") (pin "2") (pinfunction "NC_2") (pintype "unspecified+no_connect"))
    )
    (net (code "57") (name "unconnected-(D2-NC-Pad3)") (class "Default")
      (node (ref "D2") (pin "3") (pinfunction "NC_3") (pintype "unspecified+no_connect"))
    )
    (net (code "58") (name "unconnected-(U1-CAP1_NC-Pad48)") (class "Default")
      (node (ref "U1") (pin "48") (pinfunction "CAP1_NC_48") (pintype "unspecified+no_connect"))
    )
    (net (code "59") (name "unconnected-(U1-CAP2_NC-Pad47)") (class "Default")
      (node (ref "U1") (pin "47") (pinfunction "CAP2_NC_47") (pintype "unspecified+no_connect"))
    )
    (net (code "60") (name "unconnected-(U1-VDD_SDIO-Pad26)") (class "Default")
      (node (ref "U1") (pin "26") (pinfunction "VDD_SDIO_26") (pintype "unspecified+no_connect"))
    )
    (net (code "61") (name "unconnected-(U1-XTAL_N_NC-Pad44)") (class "Default")
      (node (ref "U1") (pin "44") (pinfunction "XTAL_N_NC_44") (pintype "unspecified+no_connect"))
    )
    (net (code "62") (name "unconnected-(U1-XTAL_P_NC-Pad45)") (class "Default")
      (node (ref "U1") (pin "45") (pinfunction "XTAL_P_NC_45") (pintype "unspecified+no_connect"))
    )
    (net (code "63") (name "unconnected-(U2-INT-Pad5)") (class "Default")
      (node (ref "U2") (pin "5") (pinfunction "INT_5") (pintype "unspecified+no_connect"))
    )
    (net (code "64") (name "unconnected-(U3-TNOW-Pad6)") (class "Default")
      (node (ref "U3") (pin "6") (pinfunction "TNOW_6") (pintype "unspecified+no_connect"))
    )
    (net (code "65") (name "unconnected-(U4-NC-Pad4)") (class "Default")
      (node (ref "U4") (pin "4") (pinfunction "NC_4") (pintype "unspecified+no_connect"))
    )
    (net (code "66") (name "unconnected-(USBC1-PadA2)") (class "Default")
      (node (ref "USBC1") (pin "A2") (pinfunction "A2_A2") (pintype "unspecified+no_connect"))
    )
    (net (code "67") (name "unconnected-(USBC1-PadA3)") (class "Default")
      (node (ref "USBC1") (pin "A3") (pinfunction "A3_A3") (pintype "unspecified+no_connect"))
    )
    (net (code "68") (name "unconnected-(USBC1-PadA8)") (class "Default")
      (node (ref "USBC1") (pin "A8") (pinfunction "A8_A8") (pintype "unspecified+no_connect"))
    )
    (net (code "69") (name "unconnected-(USBC1-PadA10)") (class "Default")
      (node (ref "USBC1") (pin "A10") (pinfunction "A10_A10") (pintype "unspecified+no_connect"))
    )
    (net (code "70") (name "unconnected-(USBC1-PadA11)") (class "Default")
      (node (ref "USBC1") (pin "A11") (pinfunction "A11_A11") (pintype "unspecified+no_connect"))
    )
    (net (code "71") (name "unconnected-(USBC1-PadB2)") (class "Default")
      (node (ref "USBC1") (pin "B2") (pinfunction "B2_B2") (pintype "unspecified+no_connect"))
    )
    (net (code "72") (name "unconnected-(USBC1-PadB3)") (class "Default")
      (node (ref "USBC1") (pin "B3") (pinfunction "B3_B3") (pintype "unspecified+no_connect"))
    )
    (net (code "73") (name "unconnected-(USBC1-PadB8)") (class "Default")
      (node (ref "USBC1") (pin "B8") (pinfunction "B8_B8") (pintype "unspecified+no_connect"))
    )
    (net (code "74") (name "unconnected-(USBC1-PadB10)") (class "Default")
      (node (ref "USBC1") (pin "B10") (pinfunction "B10_B10") (pintype "unspecified+no_connect"))
    )
    (net (code "75") (name "unconnected-(USBC1-PadB11)") (class "Default")
      (node (ref "USBC1") (pin "B11") (pinfunction "B11_B11") (pintype "unspecified+no_connect"))
    )
  )
)
